# 21_-_TEST_POINTS.net
KiCad netlist of a schematic drawn in Altium Designer
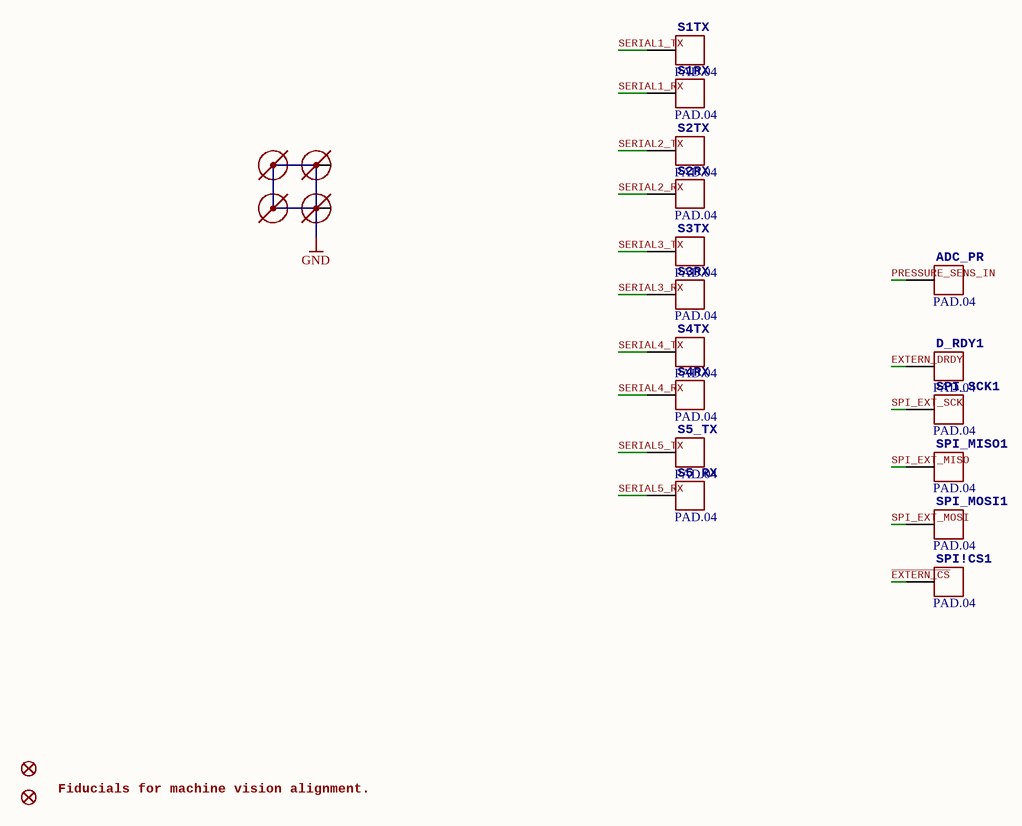
[diagram p0: [21] - TEST POINTS.SchDoc]

(export (version "E")
  (design (tool "Eeschema 10.0.6"))
  (components
    (comp (ref "ADC_PR")
      (value "PAD.04")
      (footprint "PAD.04X.04")
      (libsource (lib "pixhawk2") (part "PAD.04"))
    )
    (comp (ref "D_RDY1")
      (value "PAD.04")
      (footprint "PAD.04X.04")
      (libsource (lib "pixhawk2") (part "PAD.04"))
    )
    (comp (ref "JP400")
      (value "FIDUCIAL1.5X3")
      (footprint "FIDUCIAL-1.5X3")
      (description "<b>Fiducial Alignment Points</b>\nVarious fiducial points for machine vision alignment.")
      (libsource (lib "pixhawk2") (part "FIDUCIAL1.5X3"))
    )
    (comp (ref "JP401")
      (value "FIDUCIAL1.5X3")
      (footprint "FIDUCIAL-1.5X3")
      (description "<b>Fiducial Alignment Points</b>\nVarious fiducial points for machine vision alignment.")
      (libsource (lib "pixhawk2") (part "FIDUCIAL1.5X3"))
    )
    (comp (ref "M3_MOUNT901")
      (value "MOUNT-HOLE1.8MM")
      (footprint "MOUNT-HOLE1.8")
      (libsource (lib "pixhawk2") (part "MOUNT-HOLE1.8MM"))
    )
    (comp (ref "M3_MOUNT902")
      (value "MOUNT-HOLE1.8MM")
      (footprint "MOUNT-HOLE1.8")
      (libsource (lib "pixhawk2") (part "MOUNT-HOLE1.8MM"))
    )
    (comp (ref "M3_MOUNT903")
      (value "MOUNT-HOLE1.8MM")
      (footprint "MOUNT-HOLE1.8")
      (libsource (lib "pixhawk2") (part "MOUNT-HOLE1.8MM"))
    )
    (comp (ref "M3_MOUNT904")
      (value "MOUNT-HOLE1.8MM")
      (footprint "MOUNT-HOLE1.8")
      (libsource (lib "pixhawk2") (part "MOUNT-HOLE1.8MM"))
    )
    (comp (ref "S1RX") (value "PAD.04") (footprint "PAD.04X.04") (libsource (lib "pixhawk2") (part "PAD.04")))
    (comp (ref "S1TX") (value "PAD.04") (footprint "PAD.04X.04") (libsource (lib "pixhawk2") (part "PAD.04")))
    (comp (ref "S2RX") (value "PAD.04") (footprint "PAD.04X.04") (libsource (lib "pixhawk2") (part "PAD.04")))
    (comp (ref "S2TX") (value "PAD.04") (footprint "PAD.04X.04") (libsource (lib "pixhawk2") (part "PAD.04")))
    (comp (ref "S3RX") (value "PAD.04") (footprint "PAD.04X.04") (libsource (lib "pixhawk2") (part "PAD.04")))
    (comp (ref "S3TX") (value "PAD.04") (footprint "PAD.04X.04") (libsource (lib "pixhawk2") (part "PAD.04")))
    (comp (ref "S4RX") (value "PAD.04") (footprint "PAD.04X.04") (libsource (lib "pixhawk2") (part "PAD.04")))
    (comp (ref "S4TX") (value "PAD.04") (footprint "PAD.04X.04") (libsource (lib "pixhawk2") (part "PAD.04")))
    (comp (ref "S5_RX")
      (value "PAD.04")
      (footprint "PAD.04X.04")
      (libsource (lib "pixhawk2") (part "PAD.04"))
    )
    (comp (ref "S5_TX")
      (value "PAD.04")
      (footprint "PAD.04X.04")
      (libsource (lib "pixhawk2") (part "PAD.04"))
    )
    (comp (ref "SPI!CS1")
      (value "PAD.04")
      (footprint "PAD.04X.04")
      (libsource (lib "pixhawk2") (part "PAD.04"))
    )
    (comp (ref "SPI_MISO1")
      (value "PAD.04")
      (footprint "PAD.04X.04")
      (libsource (lib "pixhawk2") (part "PAD.04"))
    )
    (comp (ref "SPI_MOSI1")
      (value "PAD.04")
      (footprint "PAD.04X.04")
      (libsource (lib "pixhawk2") (part "PAD.04"))
    )
    (comp (ref "SPI_SCK1")
      (value "PAD.04")
      (footprint "PAD.04X.04")
      (libsource (lib "pixhawk2") (part "PAD.04"))
    )
  )
  (nets
    (net (code "1") (name "/EXTERN_DRDY") (class "Default")
      (node (ref "D_RDY1") (pin "P$1") (pinfunction "P$1_P$1") (pintype "passive"))
    )
    (net (code "2") (name "/PRESSURE_SENS_IN") (class "Default")
      (node (ref "ADC_PR") (pin "P$1") (pinfunction "P$1_P$1") (pintype "passive"))
    )
    (net (code "3") (name "/SERIAL1_RX") (class "Default")
      (node (ref "S1RX") (pin "P$1") (pinfunction "P$1_P$1") (pintype "passive"))
    )
    (net (code "4") (name "/SERIAL1_TX") (class "Default")
      (node (ref "S1TX") (pin "P$1") (pinfunction "P$1_P$1") (pintype "passive"))
    )
    (net (code "5") (name "/SERIAL2_RX") (class "Default")
      (node (ref "S2RX") (pin "P$1") (pinfunction "P$1_P$1") (pintype "passive"))
    )
    (net (code "6") (name "/SERIAL2_TX") (class "Default")
      (node (ref "S2TX") (pin "P$1") (pinfunction "P$1_P$1") (pintype "passive"))
    )
    (net (code "7") (name "/SERIAL3_RX") (class "Default")
      (node (ref "S3RX") (pin "P$1") (pinfunction "P$1_P$1") (pintype "passive"))
    )
    (net (code "8") (name "/SERIAL3_TX") (class "Default")
      (node (ref "S3TX") (pin "P$1") (pinfunction "P$1_P$1") (pintype "passive"))
    )
    (net (code "9") (name "/SERIAL4_RX") (class "Default")
      (node (ref "S4RX") (pin "P$1") (pinfunction "P$1_P$1") (pintype "passive"))
    )
    (net (code "10") (name "/SERIAL4_TX") (class "Default")
      (node (ref "S4TX") (pin "P$1") (pinfunction "P$1_P$1") (pintype "passive"))
    )
    (net (code "11") (name "/SERIAL5_RX") (class "Default")
      (node (ref "S5_RX") (pin "P$1") (pinfunction "P$1_P$1") (pintype "passive"))
    )
    (net (code "12") (name "/SERIAL5_TX") (class "Default")
      (node (ref "S5_TX") (pin "P$1") (pinfunction "P$1_P$1") (pintype "passive"))
    )
    (net (code "13") (name "/SPI_EXT_MISO") (class "Default")
      (node (ref "SPI_MISO1") (pin "P$1") (pinfunction "P$1_P$1") (pintype "passive"))
    )
    (net (code "14") (name "/SPI_EXT_MOSI") (class "Default")
      (node (ref "SPI_MOSI1") (pin "P$1") (pinfunction "P$1_P$1") (pintype "passive"))
    )
    (net (code "15") (name "/SPI_EXT_SCK") (class "Default")
      (node (ref "SPI_SCK1") (pin "P$1") (pinfunction "P$1_P$1") (pintype "passive"))
    )
    (net (code "16") (name "/~{EXTERN_CS}") (class "Default")
      (node (ref "SPI!CS1") (pin "P$1") (pinfunction "P$1_P$1") (pintype "passive"))
    )
    (net (code "17") (name "GND") (class "Default")
      (node (ref "M3_MOUNT901") (pin "1") (pinfunction "1_1") (pintype "passive"))
      (node (ref "M3_MOUNT902") (pin "1") (pinfunction "1_1") (pintype "passive"))
      (node (ref "M3_MOUNT903") (pin "1") (pinfunction "1_1") (pintype "passive"))
      (node (ref "M3_MOUNT904") (pin "1") (pinfunction "1_1") (pintype "passive"))
    )
  )
)
